# DCSource3V5.net
KiCad netlist of a schematic drawn in Altium Designer
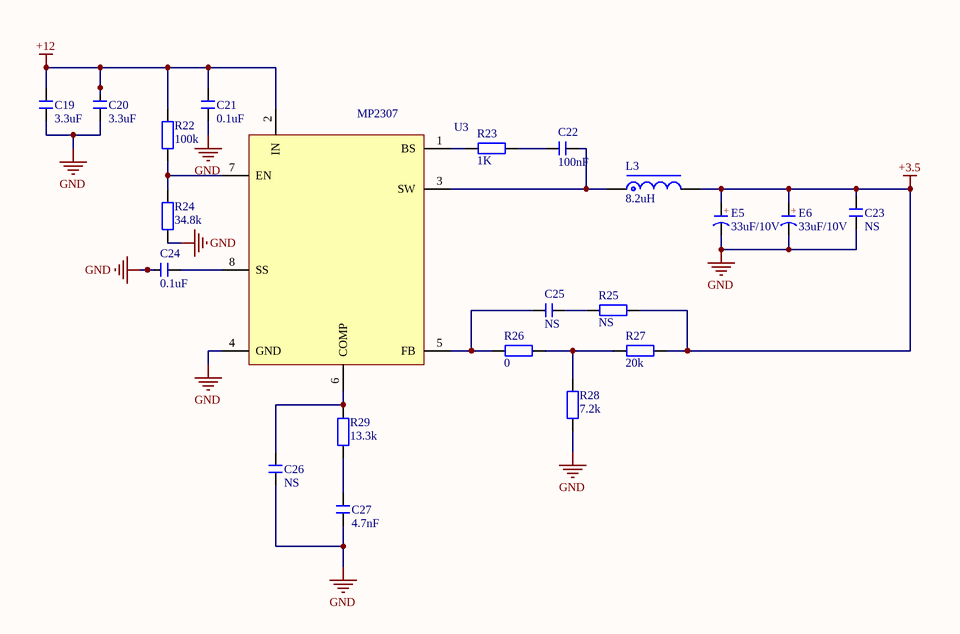
[diagram p0: DCSource3V5.SchDoc]

(export (version "E")
  (design (tool "Eeschema 10.0.6"))
  (components
    (comp (ref "C19")
      (value "3.3uF")
      (footprint "C 0805_L")
      (description "无极性贴片电容")
      (libsource (lib "电容-电阻-电感-电位器") (part "C"))
    )
    (comp (ref "C20")
      (value "3.3uF")
      (footprint "C 0805_L")
      (description "无极性贴片电容")
      (libsource (lib "电容-电阻-电感-电位器") (part "C"))
    )
    (comp (ref "C21")
      (value "0.1uF")
      (footprint "C 0805_L")
      (description "无极性贴片电容")
      (libsource (lib "电容-电阻-电感-电位器") (part "C"))
    )
    (comp (ref "C22")
      (value "100nF")
      (footprint "C 0805_L")
      (description "无极性贴片电容")
      (libsource (lib "电容-电阻-电感-电位器") (part "C"))
    )
    (comp (ref "C23")
      (value "NS")
      (footprint "C 0805_L")
      (description "无极性贴片电容")
      (libsource (lib "电容-电阻-电感-电位器") (part "C"))
    )
    (comp (ref "C24")
      (value "0.1uF")
      (footprint "C 0805_L")
      (description "无极性贴片电容")
      (libsource (lib "电容-电阻-电感-电位器") (part "C"))
    )
    (comp (ref "C25")
      (value "NS")
      (footprint "C 0805_L")
      (description "无极性贴片电容")
      (libsource (lib "电容-电阻-电感-电位器") (part "C"))
    )
    (comp (ref "C26")
      (value "NS")
      (footprint "C 0805_L")
      (description "无极性贴片电容")
      (libsource (lib "电容-电阻-电感-电位器") (part "C"))
    )
    (comp (ref "C27")
      (value "4.7nF")
      (footprint "C 0805_L")
      (description "无极性贴片电容")
      (libsource (lib "电容-电阻-电感-电位器") (part "C"))
    )
    (comp (ref "E5")
      (value "33uF/10V")
      (footprint "CT 5*6 - C")
      (description "贴片固态电容")
      (libsource (lib "电容-电阻-电感-电位器") (part "C-CT"))
    )
    (comp (ref "E6")
      (value "33uF/10V")
      (footprint "CT 5*6 - C")
      (description "贴片固态电容")
      (libsource (lib "电容-电阻-电感-电位器") (part "C-CT"))
    )
    (comp (ref "L3")
      (value "8.2uH")
      (footprint "CD31")
      (description "贴片功率电感")
      (libsource (lib "电容-电阻-电感-电位器") (part "L-CD"))
    )
    (comp (ref "R22")
      (value "100k")
      (footprint "R 0805_L")
      (description "贴片电阻")
      (libsource (lib "电容-电阻-电感-电位器") (part "R"))
    )
    (comp (ref "R23")
      (value "1K")
      (footprint "R 0805_L")
      (description "贴片电阻")
      (libsource (lib "电容-电阻-电感-电位器") (part "R"))
    )
    (comp (ref "R24")
      (value "34.8k")
      (footprint "R 0805_L")
      (description "贴片电阻")
      (libsource (lib "电容-电阻-电感-电位器") (part "R"))
    )
    (comp (ref "R25")
      (value "NS")
      (footprint "R 0805_L")
      (description "贴片电阻")
      (libsource (lib "电容-电阻-电感-电位器") (part "R"))
    )
    (comp (ref "R26")
      (value "0")
      (footprint "R 0805_L")
      (description "贴片电阻")
      (libsource (lib "电容-电阻-电感-电位器") (part "R"))
    )
    (comp (ref "R27")
      (value "20k")
      (footprint "R 0805_L")
      (description "贴片电阻")
      (libsource (lib "电容-电阻-电感-电位器") (part "R"))
    )
    (comp (ref "R28")
      (value "7.2k")
      (footprint "R 0805_L")
      (description "贴片电阻")
      (libsource (lib "电容-电阻-电感-电位器") (part "R"))
    )
    (comp (ref "R29")
      (value "13.3k")
      (footprint "R 0805_L")
      (description "贴片电阻")
      (libsource (lib "电容-电阻-电感-电位器") (part "R"))
    )
    (comp (ref "U3") (value "MP2307") (footprint "SOP8_M") (libsource (lib "Schlib1") (part "Component_1")))
  )
  (nets
    (net (code "1") (name "+3.5") (class "Default")
      (node (ref "C23") (pin "2") (pinfunction "2_2") (pintype "passive"))
      (node (ref "E5") (pin "1") (pinfunction "A_1") (pintype "passive"))
      (node (ref "E6") (pin "1") (pinfunction "A_1") (pintype "passive"))
      (node (ref "L3") (pin "2") (pinfunction "2_2") (pintype "passive"))
      (node (ref "R25") (pin "1") (pinfunction "1_1") (pintype "passive"))
      (node (ref "R27") (pin "2") (pinfunction "2_2") (pintype "passive"))
    )
    (net (code "2") (name "+12") (class "Default")
      (node (ref "C19") (pin "2") (pinfunction "2_2") (pintype "passive"))
      (node (ref "C20") (pin "2") (pinfunction "2_2") (pintype "passive"))
      (node (ref "C21") (pin "2") (pinfunction "2_2") (pintype "passive"))
      (node (ref "R22") (pin "2") (pinfunction "2_2") (pintype "passive"))
      (node (ref "U3") (pin "2") (pinfunction "IN_2") (pintype "passive"))
    )
    (net (code "3") (name "GND") (class "Default")
      (node (ref "C19") (pin "1") (pinfunction "1_1") (pintype "passive"))
      (node (ref "C20") (pin "1") (pinfunction "1_1") (pintype "passive"))
      (node (ref "C21") (pin "1") (pinfunction "1_1") (pintype "passive"))
      (node (ref "C23") (pin "1") (pinfunction "1_1") (pintype "passive"))
      (node (ref "C24") (pin "2") (pinfunction "2_2") (pintype "passive"))
      (node (ref "C26") (pin "1") (pinfunction "1_1") (pintype "passive"))
      (node (ref "C27") (pin "1") (pinfunction "1_1") (pintype "passive"))
      (node (ref "E5") (pin "2") (pinfunction "K_2") (pintype "passive"))
      (node (ref "E6") (pin "2") (pinfunction "K_2") (pintype "passive"))
      (node (ref "R24") (pin "1") (pinfunction "1_1") (pintype "passive"))
      (node (ref "R28") (pin "1") (pinfunction "1_1") (pintype "passive"))
      (node (ref "U3") (pin "4") (pinfunction "GND_4") (pintype "passive"))
    )
    (net (code "4") (name "Net-(C22-Pad1)") (class "Default")
      (node (ref "C22") (pin "1") (pinfunction "1_1") (pintype "passive"))
      (node (ref "R23") (pin "2") (pinfunction "2_2") (pintype "passive"))
    )
    (net (code "5") (name "Net-(C25-Pad2)") (class "Default")
      (node (ref "C25") (pin "2") (pinfunction "2_2") (pintype "passive"))
      (node (ref "R25") (pin "2") (pinfunction "2_2") (pintype "passive"))
    )
    (net (code "6") (name "Net-(C27-Pad2)") (class "Default")
      (node (ref "C27") (pin "2") (pinfunction "2_2") (pintype "passive"))
      (node (ref "R29") (pin "1") (pinfunction "1_1") (pintype "passive"))
    )
    (net (code "7") (name "Net-(R26-Pad2)") (class "Default")
      (node (ref "R26") (pin "2") (pinfunction "2_2") (pintype "passive"))
      (node (ref "R27") (pin "1") (pinfunction "1_1") (pintype "passive"))
      (node (ref "R28") (pin "2") (pinfunction "2_2") (pintype "passive"))
    )
    (net (code "8") (name "Net-(U3-BS)") (class "Default")
      (node (ref "R23") (pin "1") (pinfunction "1_1") (pintype "passive"))
      (node (ref "U3") (pin "1") (pinfunction "BS_1") (pintype "passive"))
    )
    (net (code "9") (name "Net-(U3-COMP)") (class "Default")
      (node (ref "C26") (pin "2") (pinfunction "2_2") (pintype "passive"))
      (node (ref "R29") (pin "2") (pinfunction "2_2") (pintype "passive"))
      (node (ref "U3") (pin "6") (pinfunction "COMP_6") (pintype "passive"))
    )
    (net (code "10") (name "Net-(U3-EN)") (class "Default")
      (node (ref "R22") (pin "1") (pinfunction "1_1") (pintype "passive"))
      (node (ref "R24") (pin "2") (pinfunction "2_2") (pintype "passive"))
      (node (ref "U3") (pin "7") (pinfunction "EN_7") (pintype "passive"))
    )
    (net (code "11") (name "Net-(U3-FB)") (class "Default")
      (node (ref "C25") (pin "1") (pinfunction "1_1") (pintype "passive"))
      (node (ref "R26") (pin "1") (pinfunction "1_1") (pintype "passive"))
      (node (ref "U3") (pin "5") (pinfunction "FB_5") (pintype "passive"))
    )
    (net (code "12") (name "Net-(U3-SS)") (class "Default")
      (node (ref "C24") (pin "1") (pinfunction "1_1") (pintype "passive"))
      (node (ref "U3") (pin "8") (pinfunction "SS_8") (pintype "passive"))
    )
    (net (code "13") (name "Net-(U3-SW)") (class "Default")
      (node (ref "C22") (pin "2") (pinfunction "2_2") (pintype "passive"))
      (node (ref "L3") (pin "1") (pinfunction "1_1") (pintype "passive"))
      (node (ref "U3") (pin "3") (pinfunction "SW_3") (pintype "passive"))
    )
  )
)
